# PowerBUS7.net
KiCad netlist of a schematic drawn in EAGLE
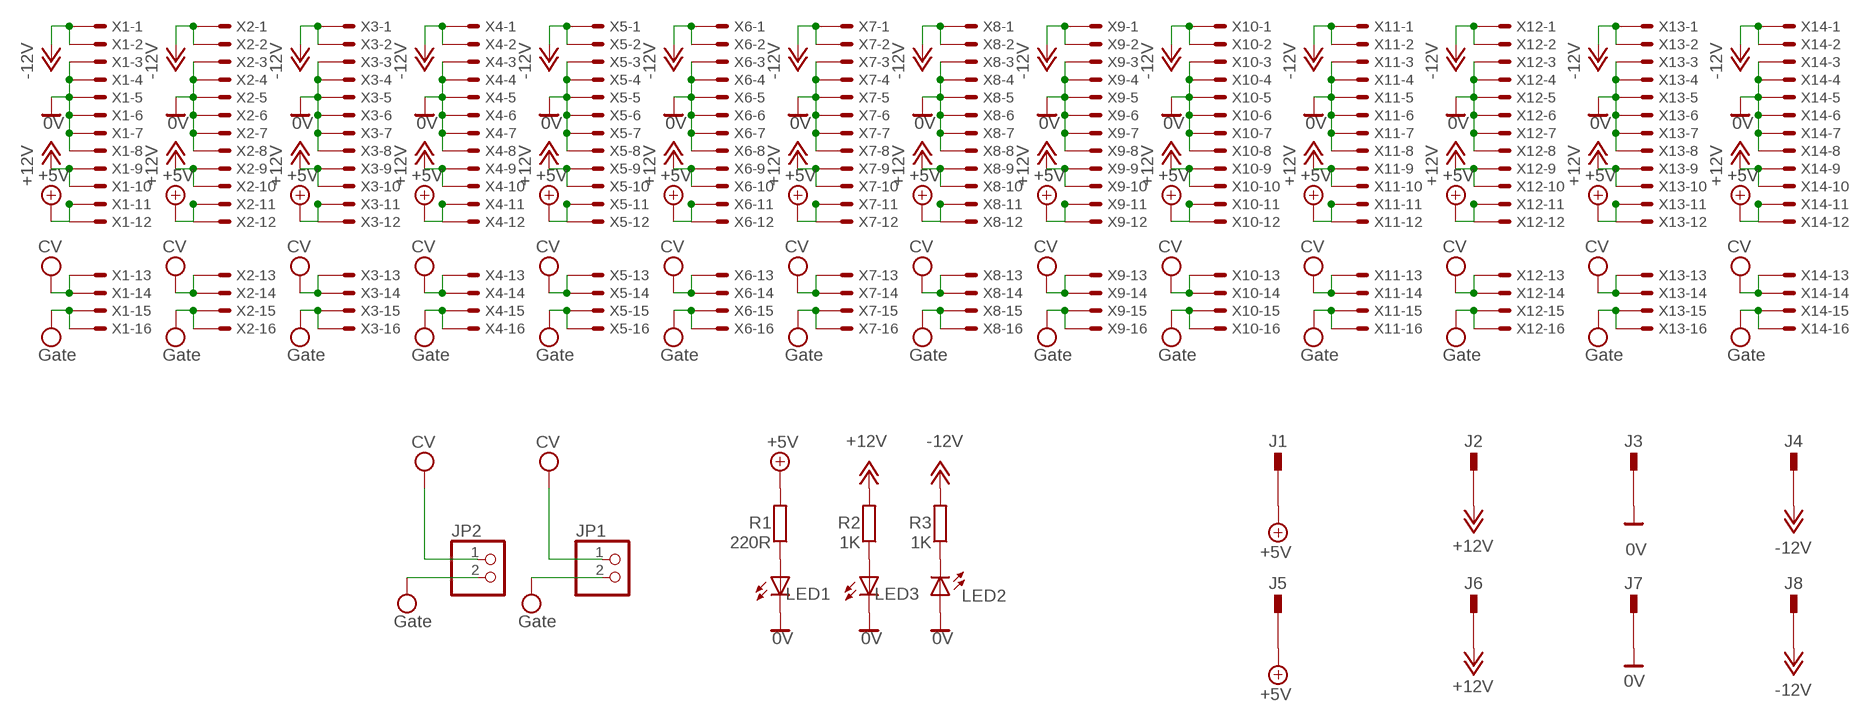
[diagram p0: schematic, sheet 1]

(export (version "E")
  (design (tool "Eeschema 10.0.6"))
  (components
    (comp (ref "J1")
      (value "PIN2F061.040")
      (footprint "eagle-import:F061.040")
      (libsource (lib "eagle-import") (part "PIN2F061.040"))
    )
    (comp (ref "J2")
      (value "PIN2F061.040")
      (footprint "eagle-import:F061.040")
      (libsource (lib "eagle-import") (part "PIN2F061.040"))
    )
    (comp (ref "J3")
      (value "PIN2F061.040")
      (footprint "eagle-import:F061.040")
      (libsource (lib "eagle-import") (part "PIN2F061.040"))
    )
    (comp (ref "J4")
      (value "PIN2F061.040")
      (footprint "eagle-import:F061.040")
      (libsource (lib "eagle-import") (part "PIN2F061.040"))
    )
    (comp (ref "J5")
      (value "PIN2F061.040")
      (footprint "eagle-import:F061.040")
      (libsource (lib "eagle-import") (part "PIN2F061.040"))
    )
    (comp (ref "J6")
      (value "PIN2F061.040")
      (footprint "eagle-import:F061.040")
      (libsource (lib "eagle-import") (part "PIN2F061.040"))
    )
    (comp (ref "J7")
      (value "PIN2F061.040")
      (footprint "eagle-import:F061.040")
      (libsource (lib "eagle-import") (part "PIN2F061.040"))
    )
    (comp (ref "J8")
      (value "PIN2F061.040")
      (footprint "eagle-import:F061.040")
      (libsource (lib "eagle-import") (part "PIN2F061.040"))
    )
    (comp (ref "JP1")
      (value "PINHD-1X2")
      (footprint "eagle-import:1X02")
      (libsource (lib "eagle-import") (part "PINHD-1X2"))
    )
    (comp (ref "JP2")
      (value "PINHD-1X2")
      (footprint "eagle-import:1X02")
      (libsource (lib "eagle-import") (part "PINHD-1X2"))
    )
    (comp (ref "LED1")
      (value "LED5MM")
      (footprint "eagle-import:LED5MM")
      (libsource (lib "eagle-import") (part "LED5MM"))
    )
    (comp (ref "LED2")
      (value "LED5MM")
      (footprint "eagle-import:LED5MM")
      (libsource (lib "eagle-import") (part "LED5MM"))
    )
    (comp (ref "LED3")
      (value "LED5MM")
      (footprint "eagle-import:LED5MM")
      (libsource (lib "eagle-import") (part "LED5MM"))
    )
    (comp (ref "R1")
      (value "220R")
      (footprint "eagle-import:0204_5")
      (libsource (lib "eagle-import") (part "R-EU_0204/5"))
    )
    (comp (ref "R2")
      (value "1K")
      (footprint "eagle-import:0204_5")
      (libsource (lib "eagle-import") (part "R-EU_0204/5"))
    )
    (comp (ref "R3")
      (value "1K")
      (footprint "eagle-import:0204_5")
      (libsource (lib "eagle-import") (part "R-EU_0204/5"))
    )
    (comp (ref "X1")
      (value "057-016-1")
      (footprint "eagle-import:057-016-1")
      (libsource (lib "eagle-import") (part "057-016-1"))
    )
    (comp (ref "X2")
      (value "057-016-1")
      (footprint "eagle-import:057-016-1")
      (libsource (lib "eagle-import") (part "057-016-1"))
    )
    (comp (ref "X3")
      (value "057-016-1")
      (footprint "eagle-import:057-016-1")
      (libsource (lib "eagle-import") (part "057-016-1"))
    )
    (comp (ref "X4")
      (value "057-016-1")
      (footprint "eagle-import:057-016-1")
      (libsource (lib "eagle-import") (part "057-016-1"))
    )
    (comp (ref "X5")
      (value "057-016-1")
      (footprint "eagle-import:057-016-1")
      (libsource (lib "eagle-import") (part "057-016-1"))
    )
    (comp (ref "X6")
      (value "057-016-1")
      (footprint "eagle-import:057-016-1")
      (libsource (lib "eagle-import") (part "057-016-1"))
    )
    (comp (ref "X7")
      (value "057-016-1")
      (footprint "eagle-import:057-016-1")
      (libsource (lib "eagle-import") (part "057-016-1"))
    )
    (comp (ref "X8")
      (value "057-016-1")
      (footprint "eagle-import:057-016-1")
      (libsource (lib "eagle-import") (part "057-016-1"))
    )
    (comp (ref "X9")
      (value "057-016-1")
      (footprint "eagle-import:057-016-1")
      (libsource (lib "eagle-import") (part "057-016-1"))
    )
    (comp (ref "X10")
      (value "057-016-1")
      (footprint "eagle-import:057-016-1")
      (libsource (lib "eagle-import") (part "057-016-1"))
    )
    (comp (ref "X11")
      (value "057-016-1")
      (footprint "eagle-import:057-016-1")
      (libsource (lib "eagle-import") (part "057-016-1"))
    )
    (comp (ref "X12")
      (value "057-016-1")
      (footprint "eagle-import:057-016-1")
      (libsource (lib "eagle-import") (part "057-016-1"))
    )
    (comp (ref "X13")
      (value "057-016-1")
      (footprint "eagle-import:057-016-1")
      (libsource (lib "eagle-import") (part "057-016-1"))
    )
    (comp (ref "X14")
      (value "057-016-1")
      (footprint "eagle-import:057-016-1")
      (libsource (lib "eagle-import") (part "057-016-1"))
    )
  )
  (nets
    (net (code "1") (name "+5V") (class "Default")
      (node (ref "J1") (pin "A1") (pinfunction "1_A1") (pintype "passive"))
      (node (ref "J1") (pin "A2") (pinfunction "1_A2") (pintype "passive"))
      (node (ref "J5") (pin "A1") (pinfunction "1_A1") (pintype "passive"))
      (node (ref "J5") (pin "A2") (pinfunction "1_A2") (pintype "passive"))
      (node (ref "R1") (pin "2") (pinfunction "2_2") (pintype "passive"))
      (node (ref "X1") (pin "11") (pinfunction "S_11") (pintype "passive"))
      (node (ref "X1") (pin "12") (pinfunction "S_12") (pintype "passive"))
      (node (ref "X10") (pin "11") (pinfunction "S_11") (pintype "passive"))
      (node (ref "X10") (pin "12") (pinfunction "S_12") (pintype "passive"))
      (node (ref "X11") (pin "11") (pinfunction "S_11") (pintype "passive"))
      (node (ref "X11") (pin "12") (pinfunction "S_12") (pintype "passive"))
      (node (ref "X12") (pin "11") (pinfunction "S_11") (pintype "passive"))
      (node (ref "X12") (pin "12") (pinfunction "S_12") (pintype "passive"))
      (node (ref "X13") (pin "11") (pinfunction "S_11") (pintype "passive"))
      (node (ref "X13") (pin "12") (pinfunction "S_12") (pintype "passive"))
      (node (ref "X14") (pin "11") (pinfunction "S_11") (pintype "passive"))
      (node (ref "X14") (pin "12") (pinfunction "S_12") (pintype "passive"))
      (node (ref "X2") (pin "11") (pinfunction "S_11") (pintype "passive"))
      (node (ref "X2") (pin "12") (pinfunction "S_12") (pintype "passive"))
      (node (ref "X3") (pin "11") (pinfunction "S_11") (pintype "passive"))
      (node (ref "X3") (pin "12") (pinfunction "S_12") (pintype "passive"))
      (node (ref "X4") (pin "11") (pinfunction "S_11") (pintype "passive"))
      (node (ref "X4") (pin "12") (pinfunction "S_12") (pintype "passive"))
      (node (ref "X5") (pin "11") (pinfunction "S_11") (pintype "passive"))
      (node (ref "X5") (pin "12") (pinfunction "S_12") (pintype "passive"))
      (node (ref "X6") (pin "11") (pinfunction "S_11") (pintype "passive"))
      (node (ref "X6") (pin "12") (pinfunction "S_12") (pintype "passive"))
      (node (ref "X7") (pin "11") (pinfunction "S_11") (pintype "passive"))
      (node (ref "X7") (pin "12") (pinfunction "S_12") (pintype "passive"))
      (node (ref "X8") (pin "11") (pinfunction "S_11") (pintype "passive"))
      (node (ref "X8") (pin "12") (pinfunction "S_12") (pintype "passive"))
      (node (ref "X9") (pin "11") (pinfunction "S_11") (pintype "passive"))
      (node (ref "X9") (pin "12") (pinfunction "S_12") (pintype "passive"))
    )
    (net (code "2") (name "+12V") (class "Default")
      (node (ref "J2") (pin "A1") (pinfunction "1_A1") (pintype "passive"))
      (node (ref "J2") (pin "A2") (pinfunction "1_A2") (pintype "passive"))
      (node (ref "J6") (pin "A1") (pinfunction "1_A1") (pintype "passive"))
      (node (ref "J6") (pin "A2") (pinfunction "1_A2") (pintype "passive"))
      (node (ref "R2") (pin "2") (pinfunction "2_2") (pintype "passive"))
      (node (ref "X1") (pin "10") (pinfunction "S_10") (pintype "passive"))
      (node (ref "X1") (pin "9") (pinfunction "S_9") (pintype "passive"))
      (node (ref "X10") (pin "10") (pinfunction "S_10") (pintype "passive"))
      (node (ref "X10") (pin "9") (pinfunction "S_9") (pintype "passive"))
      (node (ref "X11") (pin "10") (pinfunction "S_10") (pintype "passive"))
      (node (ref "X11") (pin "9") (pinfunction "S_9") (pintype "passive"))
      (node (ref "X12") (pin "10") (pinfunction "S_10") (pintype "passive"))
      (node (ref "X12") (pin "9") (pinfunction "S_9") (pintype "passive"))
      (node (ref "X13") (pin "10") (pinfunction "S_10") (pintype "passive"))
      (node (ref "X13") (pin "9") (pinfunction "S_9") (pintype "passive"))
      (node (ref "X14") (pin "10") (pinfunction "S_10") (pintype "passive"))
      (node (ref "X14") (pin "9") (pinfunction "S_9") (pintype "passive"))
      (node (ref "X2") (pin "10") (pinfunction "S_10") (pintype "passive"))
      (node (ref "X2") (pin "9") (pinfunction "S_9") (pintype "passive"))
      (node (ref "X3") (pin "10") (pinfunction "S_10") (pintype "passive"))
      (node (ref "X3") (pin "9") (pinfunction "S_9") (pintype "passive"))
      (node (ref "X4") (pin "10") (pinfunction "S_10") (pintype "passive"))
      (node (ref "X4") (pin "9") (pinfunction "S_9") (pintype "passive"))
      (node (ref "X5") (pin "10") (pinfunction "S_10") (pintype "passive"))
      (node (ref "X5") (pin "9") (pinfunction "S_9") (pintype "passive"))
      (node (ref "X6") (pin "10") (pinfunction "S_10") (pintype "passive"))
      (node (ref "X6") (pin "9") (pinfunction "S_9") (pintype "passive"))
      (node (ref "X7") (pin "10") (pinfunction "S_10") (pintype "passive"))
      (node (ref "X7") (pin "9") (pinfunction "S_9") (pintype "passive"))
      (node (ref "X8") (pin "10") (pinfunction "S_10") (pintype "passive"))
      (node (ref "X8") (pin "9") (pinfunction "S_9") (pintype "passive"))
      (node (ref "X9") (pin "10") (pinfunction "S_10") (pintype "passive"))
      (node (ref "X9") (pin "9") (pinfunction "S_9") (pintype "passive"))
    )
    (net (code "3") (name "-12V") (class "Default")
      (node (ref "J4") (pin "A1") (pinfunction "1_A1") (pintype "passive"))
      (node (ref "J4") (pin "A2") (pinfunction "1_A2") (pintype "passive"))
      (node (ref "J8") (pin "A1") (pinfunction "1_A1") (pintype "passive"))
      (node (ref "J8") (pin "A2") (pinfunction "1_A2") (pintype "passive"))
      (node (ref "R3") (pin "2") (pinfunction "2_2") (pintype "passive"))
      (node (ref "X1") (pin "1") (pinfunction "S_1") (pintype "passive"))
      (node (ref "X1") (pin "2") (pinfunction "S_2") (pintype "passive"))
      (node (ref "X10") (pin "1") (pinfunction "S_1") (pintype "passive"))
      (node (ref "X10") (pin "2") (pinfunction "S_2") (pintype "passive"))
      (node (ref "X11") (pin "1") (pinfunction "S_1") (pintype "passive"))
      (node (ref "X11") (pin "2") (pinfunction "S_2") (pintype "passive"))
      (node (ref "X12") (pin "1") (pinfunction "S_1") (pintype "passive"))
      (node (ref "X12") (pin "2") (pinfunction "S_2") (pintype "passive"))
      (node (ref "X13") (pin "1") (pinfunction "S_1") (pintype "passive"))
      (node (ref "X13") (pin "2") (pinfunction "S_2") (pintype "passive"))
      (node (ref "X14") (pin "1") (pinfunction "S_1") (pintype "passive"))
      (node (ref "X14") (pin "2") (pinfunction "S_2") (pintype "passive"))
      (node (ref "X2") (pin "1") (pinfunction "S_1") (pintype "passive"))
      (node (ref "X2") (pin "2") (pinfunction "S_2") (pintype "passive"))
      (node (ref "X3") (pin "1") (pinfunction "S_1") (pintype "passive"))
      (node (ref "X3") (pin "2") (pinfunction "S_2") (pintype "passive"))
      (node (ref "X4") (pin "1") (pinfunction "S_1") (pintype "passive"))
      (node (ref "X4") (pin "2") (pinfunction "S_2") (pintype "passive"))
      (node (ref "X5") (pin "1") (pinfunction "S_1") (pintype "passive"))
      (node (ref "X5") (pin "2") (pinfunction "S_2") (pintype "passive"))
      (node (ref "X6") (pin "1") (pinfunction "S_1") (pintype "passive"))
      (node (ref "X6") (pin "2") (pinfunction "S_2") (pintype "passive"))
      (node (ref "X7") (pin "1") (pinfunction "S_1") (pintype "passive"))
      (node (ref "X7") (pin "2") (pinfunction "S_2") (pintype "passive"))
      (node (ref "X8") (pin "1") (pinfunction "S_1") (pintype "passive"))
      (node (ref "X8") (pin "2") (pinfunction "S_2") (pintype "passive"))
      (node (ref "X9") (pin "1") (pinfunction "S_1") (pintype "passive"))
      (node (ref "X9") (pin "2") (pinfunction "S_2") (pintype "passive"))
    )
    (net (code "4") (name "0V") (class "Default")
      (node (ref "J3") (pin "A1") (pinfunction "1_A1") (pintype "passive"))
      (node (ref "J3") (pin "A2") (pinfunction "1_A2") (pintype "passive"))
      (node (ref "J7") (pin "A1") (pinfunction "1_A1") (pintype "passive"))
      (node (ref "J7") (pin "A2") (pinfunction "1_A2") (pintype "passive"))
      (node (ref "LED1") (pin "K") (pinfunction "C_K") (pintype "passive"))
      (node (ref "LED2") (pin "A") (pinfunction "A_A") (pintype "passive"))
      (node (ref "LED3") (pin "K") (pinfunction "C_K") (pintype "passive"))
      (node (ref "X1") (pin "3") (pinfunction "S_3") (pintype "passive"))
      (node (ref "X1") (pin "4") (pinfunction "S_4") (pintype "passive"))
      (node (ref "X1") (pin "5") (pinfunction "S_5") (pintype "passive"))
      (node (ref "X1") (pin "6") (pinfunction "S_6") (pintype "passive"))
      (node (ref "X1") (pin "7") (pinfunction "S_7") (pintype "passive"))
      (node (ref "X1") (pin "8") (pinfunction "S_8") (pintype "passive"))
      (node (ref "X10") (pin "3") (pinfunction "S_3") (pintype "passive"))
      (node (ref "X10") (pin "4") (pinfunction "S_4") (pintype "passive"))
      (node (ref "X10") (pin "5") (pinfunction "S_5") (pintype "passive"))
      (node (ref "X10") (pin "6") (pinfunction "S_6") (pintype "passive"))
      (node (ref "X10") (pin "7") (pinfunction "S_7") (pintype "passive"))
      (node (ref "X10") (pin "8") (pinfunction "S_8") (pintype "passive"))
      (node (ref "X11") (pin "3") (pinfunction "S_3") (pintype "passive"))
      (node (ref "X11") (pin "4") (pinfunction "S_4") (pintype "passive"))
      (node (ref "X11") (pin "5") (pinfunction "S_5") (pintype "passive"))
      (node (ref "X11") (pin "6") (pinfunction "S_6") (pintype "passive"))
      (node (ref "X11") (pin "7") (pinfunction "S_7") (pintype "passive"))
      (node (ref "X11") (pin "8") (pinfunction "S_8") (pintype "passive"))
      (node (ref "X12") (pin "3") (pinfunction "S_3") (pintype "passive"))
      (node (ref "X12") (pin "4") (pinfunction "S_4") (pintype "passive"))
      (node (ref "X12") (pin "5") (pinfunction "S_5") (pintype "passive"))
      (node (ref "X12") (pin "6") (pinfunction "S_6") (pintype "passive"))
      (node (ref "X12") (pin "7") (pinfunction "S_7") (pintype "passive"))
      (node (ref "X12") (pin "8") (pinfunction "S_8") (pintype "passive"))
      (node (ref "X13") (pin "3") (pinfunction "S_3") (pintype "passive"))
      (node (ref "X13") (pin "4") (pinfunction "S_4") (pintype "passive"))
      (node (ref "X13") (pin "5") (pinfunction "S_5") (pintype "passive"))
      (node (ref "X13") (pin "6") (pinfunction "S_6") (pintype "passive"))
      (node (ref "X13") (pin "7") (pinfunction "S_7") (pintype "passive"))
      (node (ref "X13") (pin "8") (pinfunction "S_8") (pintype "passive"))
      (node (ref "X14") (pin "3") (pinfunction "S_3") (pintype "passive"))
      (node (ref "X14") (pin "4") (pinfunction "S_4") (pintype "passive"))
      (node (ref "X14") (pin "5") (pinfunction "S_5") (pintype "passive"))
      (node (ref "X14") (pin "6") (pinfunction "S_6") (pintype "passive"))
      (node (ref "X14") (pin "7") (pinfunction "S_7") (pintype "passive"))
      (node (ref "X14") (pin "8") (pinfunction "S_8") (pintype "passive"))
      (node (ref "X2") (pin "3") (pinfunction "S_3") (pintype "passive"))
      (node (ref "X2") (pin "4") (pinfunction "S_4") (pintype "passive"))
      (node (ref "X2") (pin "5") (pinfunction "S_5") (pintype "passive"))
      (node (ref "X2") (pin "6") (pinfunction "S_6") (pintype "passive"))
      (node (ref "X2") (pin "7") (pinfunction "S_7") (pintype "passive"))
      (node (ref "X2") (pin "8") (pinfunction "S_8") (pintype "passive"))
      (node (ref "X3") (pin "3") (pinfunction "S_3") (pintype "passive"))
      (node (ref "X3") (pin "4") (pinfunction "S_4") (pintype "passive"))
      (node (ref "X3") (pin "5") (pinfunction "S_5") (pintype "passive"))
      (node (ref "X3") (pin "6") (pinfunction "S_6") (pintype "passive"))
      (node (ref "X3") (pin "7") (pinfunction "S_7") (pintype "passive"))
      (node (ref "X3") (pin "8") (pinfunction "S_8") (pintype "passive"))
      (node (ref "X4") (pin "3") (pinfunction "S_3") (pintype "passive"))
      (node (ref "X4") (pin "4") (pinfunction "S_4") (pintype "passive"))
      (node (ref "X4") (pin "5") (pinfunction "S_5") (pintype "passive"))
      (node (ref "X4") (pin "6") (pinfunction "S_6") (pintype "passive"))
      (node (ref "X4") (pin "7") (pinfunction "S_7") (pintype "passive"))
      (node (ref "X4") (pin "8") (pinfunction "S_8") (pintype "passive"))
      (node (ref "X5") (pin "3") (pinfunction "S_3") (pintype "passive"))
      (node (ref "X5") (pin "4") (pinfunction "S_4") (pintype "passive"))
      (node (ref "X5") (pin "5") (pinfunction "S_5") (pintype "passive"))
      (node (ref "X5") (pin "6") (pinfunction "S_6") (pintype "passive"))
      (node (ref "X5") (pin "7") (pinfunction "S_7") (pintype "passive"))
      (node (ref "X5") (pin "8") (pinfunction "S_8") (pintype "passive"))
      (node (ref "X6") (pin "3") (pinfunction "S_3") (pintype "passive"))
      (node (ref "X6") (pin "4") (pinfunction "S_4") (pintype "passive"))
      (node (ref "X6") (pin "5") (pinfunction "S_5") (pintype "passive"))
      (node (ref "X6") (pin "6") (pinfunction "S_6") (pintype "passive"))
      (node (ref "X6") (pin "7") (pinfunction "S_7") (pintype "passive"))
      (node (ref "X6") (pin "8") (pinfunction "S_8") (pintype "passive"))
      (node (ref "X7") (pin "3") (pinfunction "S_3") (pintype "passive"))
      (node (ref "X7") (pin "4") (pinfunction "S_4") (pintype "passive"))
      (node (ref "X7") (pin "5") (pinfunction "S_5") (pintype "passive"))
      (node (ref "X7") (pin "6") (pinfunction "S_6") (pintype "passive"))
      (node (ref "X7") (pin "7") (pinfunction "S_7") (pintype "passive"))
      (node (ref "X7") (pin "8") (pinfunction "S_8") (pintype "passive"))
      (node (ref "X8") (pin "3") (pinfunction "S_3") (pintype "passive"))
      (node (ref "X8") (pin "4") (pinfunction "S_4") (pintype "passive"))
      (node (ref "X8") (pin "5") (pinfunction "S_5") (pintype "passive"))
      (node (ref "X8") (pin "6") (pinfunction "S_6") (pintype "passive"))
      (node (ref "X8") (pin "7") (pinfunction "S_7") (pintype "passive"))
      (node (ref "X8") (pin "8") (pinfunction "S_8") (pintype "passive"))
      (node (ref "X9") (pin "3") (pinfunction "S_3") (pintype "passive"))
      (node (ref "X9") (pin "4") (pinfunction "S_4") (pintype "passive"))
      (node (ref "X9") (pin "5") (pinfunction "S_5") (pintype "passive"))
      (node (ref "X9") (pin "6") (pinfunction "S_6") (pintype "passive"))
      (node (ref "X9") (pin "7") (pinfunction "S_7") (pintype "passive"))
      (node (ref "X9") (pin "8") (pinfunction "S_8") (pintype "passive"))
    )
    (net (code "5") (name "CV") (class "Default")
      (node (ref "JP1") (pin "1") (pinfunction "1_1") (pintype "passive"))
      (node (ref "JP2") (pin "1") (pinfunction "1_1") (pintype "passive"))
      (node (ref "X1") (pin "13") (pinfunction "S_13") (pintype "passive"))
      (node (ref "X1") (pin "14") (pinfunction "S_14") (pintype "passive"))
      (node (ref "X10") (pin "13") (pinfunction "S_13") (pintype "passive"))
      (node (ref "X10") (pin "14") (pinfunction "S_14") (pintype "passive"))
      (node (ref "X11") (pin "13") (pinfunction "S_13") (pintype "passive"))
      (node (ref "X11") (pin "14") (pinfunction "S_14") (pintype "passive"))
      (node (ref "X12") (pin "13") (pinfunction "S_13") (pintype "passive"))
      (node (ref "X12") (pin "14") (pinfunction "S_14") (pintype "passive"))
      (node (ref "X13") (pin "13") (pinfunction "S_13") (pintype "passive"))
      (node (ref "X13") (pin "14") (pinfunction "S_14") (pintype "passive"))
      (node (ref "X14") (pin "13") (pinfunction "S_13") (pintype "passive"))
      (node (ref "X14") (pin "14") (pinfunction "S_14") (pintype "passive"))
      (node (ref "X2") (pin "13") (pinfunction "S_13") (pintype "passive"))
      (node (ref "X2") (pin "14") (pinfunction "S_14") (pintype "passive"))
      (node (ref "X3") (pin "13") (pinfunction "S_13") (pintype "passive"))
      (node (ref "X3") (pin "14") (pinfunction "S_14") (pintype "passive"))
      (node (ref "X4") (pin "13") (pinfunction "S_13") (pintype "passive"))
      (node (ref "X4") (pin "14") (pinfunction "S_14") (pintype "passive"))
      (node (ref "X5") (pin "13") (pinfunction "S_13") (pintype "passive"))
      (node (ref "X5") (pin "14") (pinfunction "S_14") (pintype "passive"))
      (node (ref "X6") (pin "13") (pinfunction "S_13") (pintype "passive"))
      (node (ref "X6") (pin "14") (pinfunction "S_14") (pintype "passive"))
      (node (ref "X7") (pin "13") (pinfunction "S_13") (pintype "passive"))
      (node (ref "X7") (pin "14") (pinfunction "S_14") (pintype "passive"))
      (node (ref "X8") (pin "13") (pinfunction "S_13") (pintype "passive"))
      (node (ref "X8") (pin "14") (pinfunction "S_14") (pintype "passive"))
      (node (ref "X9") (pin "13") (pinfunction "S_13") (pintype "passive"))
      (node (ref "X9") (pin "14") (pinfunction "S_14") (pintype "passive"))
    )
    (net (code "6") (name "Gate") (class "Default")
      (node (ref "JP1") (pin "2") (pinfunction "2_2") (pintype "passive"))
      (node (ref "JP2") (pin "2") (pinfunction "2_2") (pintype "passive"))
      (node (ref "X1") (pin "15") (pinfunction "S_15") (pintype "passive"))
      (node (ref "X1") (pin "16") (pinfunction "S_16") (pintype "passive"))
      (node (ref "X10") (pin "15") (pinfunction "S_15") (pintype "passive"))
      (node (ref "X10") (pin "16") (pinfunction "S_16") (pintype "passive"))
      (node (ref "X11") (pin "15") (pinfunction "S_15") (pintype "passive"))
      (node (ref "X11") (pin "16") (pinfunction "S_16") (pintype "passive"))
      (node (ref "X12") (pin "15") (pinfunction "S_15") (pintype "passive"))
      (node (ref "X12") (pin "16") (pinfunction "S_16") (pintype "passive"))
      (node (ref "X13") (pin "15") (pinfunction "S_15") (pintype "passive"))
      (node (ref "X13") (pin "16") (pinfunction "S_16") (pintype "passive"))
      (node (ref "X14") (pin "15") (pinfunction "S_15") (pintype "passive"))
      (node (ref "X14") (pin "16") (pinfunction "S_16") (pintype "passive"))
      (node (ref "X2") (pin "15") (pinfunction "S_15") (pintype "passive"))
      (node (ref "X2") (pin "16") (pinfunction "S_16") (pintype "passive"))
      (node (ref "X3") (pin "15") (pinfunction "S_15") (pintype "passive"))
      (node (ref "X3") (pin "16") (pinfunction "S_16") (pintype "passive"))
      (node (ref "X4") (pin "15") (pinfunction "S_15") (pintype "passive"))
      (node (ref "X4") (pin "16") (pinfunction "S_16") (pintype "passive"))
      (node (ref "X5") (pin "15") (pinfunction "S_15") (pintype "passive"))
      (node (ref "X5") (pin "16") (pinfunction "S_16") (pintype "passive"))
      (node (ref "X6") (pin "15") (pinfunction "S_15") (pintype "passive"))
      (node (ref "X6") (pin "16") (pinfunction "S_16") (pintype "passive"))
      (node (ref "X7") (pin "15") (pinfunction "S_15") (pintype "passive"))
      (node (ref "X7") (pin "16") (pinfunction "S_16") (pintype "passive"))
      (node (ref "X8") (pin "15") (pinfunction "S_15") (pintype "passive"))
      (node (ref "X8") (pin "16") (pinfunction "S_16") (pintype "passive"))
      (node (ref "X9") (pin "15") (pinfunction "S_15") (pintype "passive"))
      (node (ref "X9") (pin "16") (pinfunction "S_16") (pintype "passive"))
    )
    (net (code "7") (name "Net-(LED1-PadA)") (class "Default")
      (node (ref "LED1") (pin "A") (pinfunction "A_A") (pintype "passive"))
      (node (ref "R1") (pin "1") (pinfunction "1_1") (pintype "passive"))
    )
    (net (code "8") (name "Net-(LED2-C)") (class "Default")
      (node (ref "LED2") (pin "K") (pinfunction "C_K") (pintype "passive"))
      (node (ref "R3") (pin "1") (pinfunction "1_1") (pintype "passive"))
    )
    (net (code "9") (name "Net-(LED3-PadA)") (class "Default")
      (node (ref "LED3") (pin "A") (pinfunction "A_A") (pintype "passive"))
      (node (ref "R2") (pin "1") (pinfunction "1_1") (pintype "passive"))
    )
  )
)
